# PCB.net
KiCad netlist of a schematic drawn in Altium Designer
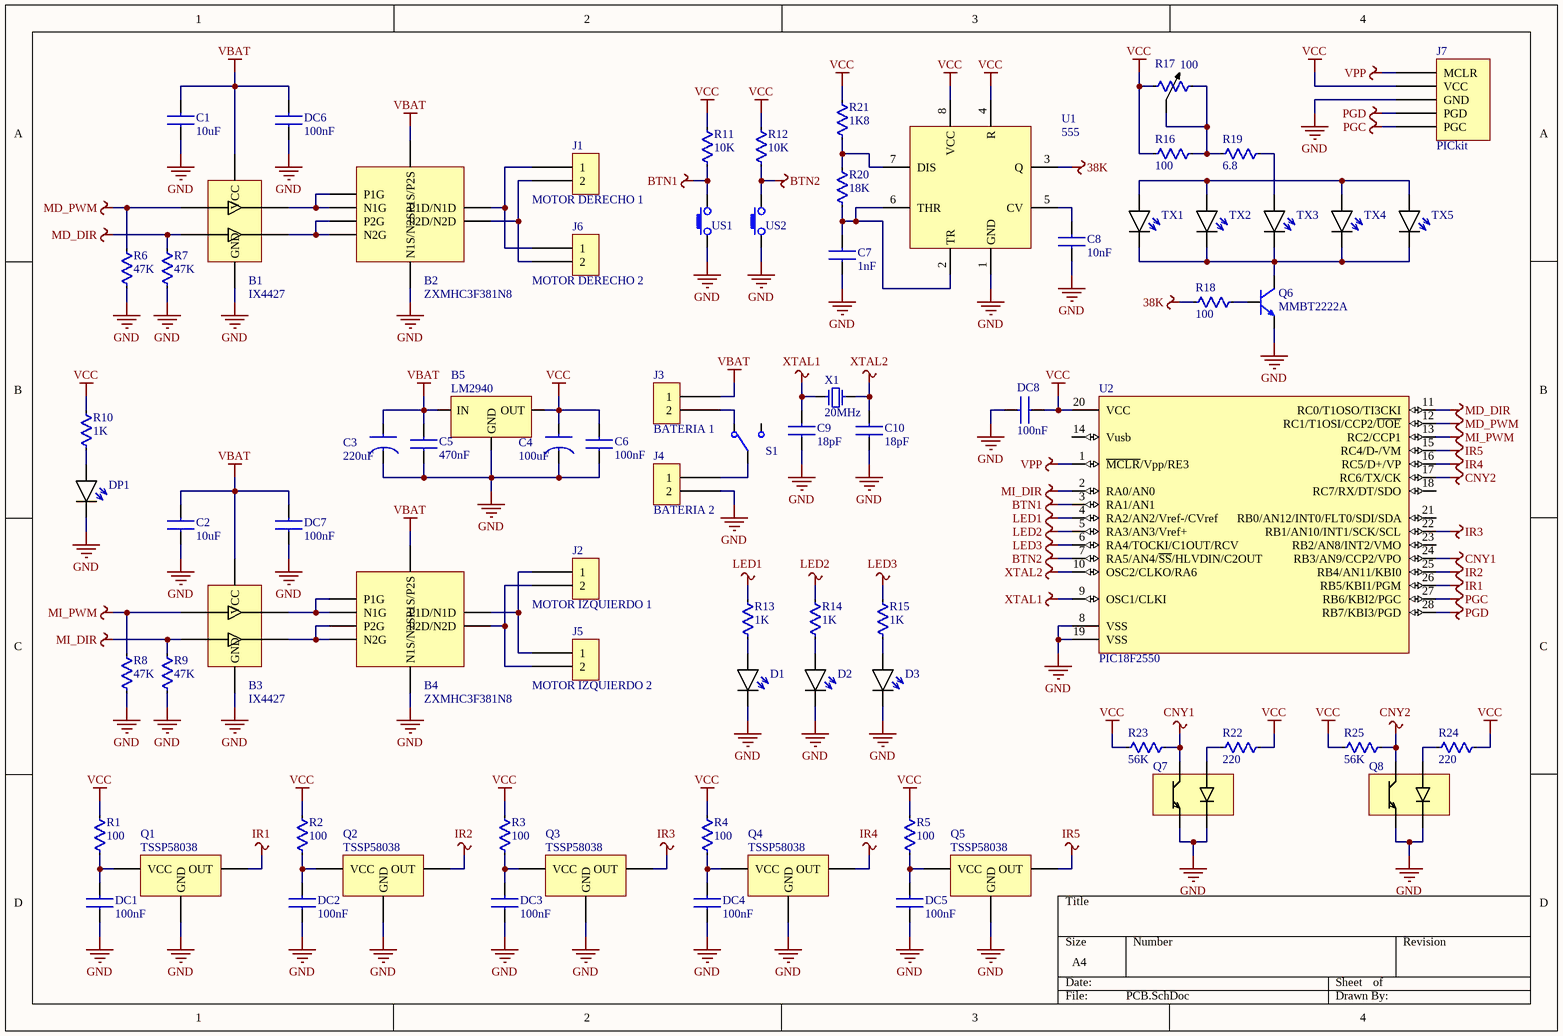
[diagram p0: PCB.SchDoc]

(export (version "E")
  (design (tool "Eeschema 10.0.6"))
  (components
    (comp (ref "B1") (value "IX4427") (footprint "SOIC-8") (libsource (lib "AltiumLibrary") (part "4427")))
    (comp (ref "B2")
      (value "ZXMHC3F381N8")
      (footprint "SOIC-8")
      (libsource (lib "AltiumLibrary") (part "ZXMHC3F381N8"))
    )
    (comp (ref "B3") (value "IX4427") (footprint "SOIC-8") (libsource (lib "AltiumLibrary") (part "4427")))
    (comp (ref "B4")
      (value "ZXMHC3F381N8")
      (footprint "SOIC-8")
      (libsource (lib "AltiumLibrary") (part "ZXMHC3F381N8"))
    )
    (comp (ref "B5") (value "LM2940") (footprint "TO-263") (libsource (lib "AltiumLibrary") (part "LM2940")))
    (comp (ref "C1")
      (value "10uF")
      (footprint "C1206")
      (fields (field (name "Comment") "CAP-CER"))
      (libsource (lib "AltiumLibrary") (part "CAP-CER"))
    )
    (comp (ref "C2")
      (value "10uF")
      (footprint "C1206")
      (fields (field (name "Comment") "CAP-CER"))
      (libsource (lib "AltiumLibrary") (part "CAP-CER"))
    )
    (comp (ref "C3")
      (value "220uF")
      (footprint "CAP-ELEC-5x11x2mm")
      (fields (field (name "Comment") "CAP-ELEC"))
      (libsource (lib "AltiumLibrary") (part "CAP-ELEC"))
    )
    (comp (ref "C4")
      (value "100uF")
      (footprint "CAP-ELEC-5x11x2mm")
      (fields (field (name "Comment") "CAP-ELEC"))
      (libsource (lib "AltiumLibrary") (part "CAP-ELEC"))
    )
    (comp (ref "C5")
      (value "470nF")
      (footprint "C1206")
      (fields (field (name "Comment") "CAP-CER"))
      (libsource (lib "AltiumLibrary") (part "CAP-CER"))
    )
    (comp (ref "C6")
      (value "100nF")
      (footprint "C1206")
      (fields (field (name "Comment") "CAP-CER"))
      (libsource (lib "AltiumLibrary") (part "CAP-CER"))
    )
    (comp (ref "C7")
      (value "1nF")
      (footprint "C1206")
      (fields (field (name "Comment") "CAP-CER"))
      (libsource (lib "AltiumLibrary") (part "CAP-CER"))
    )
    (comp (ref "C8")
      (value "10nF")
      (footprint "C1206")
      (fields (field (name "Comment") "CAP-CER"))
      (libsource (lib "AltiumLibrary") (part "CAP-CER"))
    )
    (comp (ref "C9")
      (value "18pF")
      (footprint "C1206")
      (fields (field (name "Comment") "CAP-CER"))
      (libsource (lib "AltiumLibrary") (part "CAP-CER"))
    )
    (comp (ref "C10")
      (value "18pF")
      (footprint "C1206")
      (fields (field (name "Comment") "CAP-CER"))
      (libsource (lib "AltiumLibrary") (part "CAP-CER"))
    )
    (comp (ref "D1") (value "LED") (footprint "LED-3MM-RED") (libsource (lib "AltiumLibrary") (part "LED")))
    (comp (ref "D2")
      (value "LED")
      (footprint "LED-3MM-YELLOW")
      (libsource (lib "AltiumLibrary") (part "LED"))
    )
    (comp (ref "D3") (value "LED") (footprint "LED-3MM-GREEN") (libsource (lib "AltiumLibrary") (part "LED")))
    (comp (ref "DC1")
      (value "100nF")
      (footprint "C1206")
      (fields (field (name "Comment") "CAP-CER"))
      (libsource (lib "AltiumLibrary") (part "CAP-CER"))
    )
    (comp (ref "DC2")
      (value "100nF")
      (footprint "C1206")
      (fields (field (name "Comment") "CAP-CER"))
      (libsource (lib "AltiumLibrary") (part "CAP-CER"))
    )
    (comp (ref "DC3")
      (value "100nF")
      (footprint "C1206")
      (fields (field (name "Comment") "CAP-CER"))
      (libsource (lib "AltiumLibrary") (part "CAP-CER"))
    )
    (comp (ref "DC4")
      (value "100nF")
      (footprint "C1206")
      (fields (field (name "Comment") "CAP-CER"))
      (libsource (lib "AltiumLibrary") (part "CAP-CER"))
    )
    (comp (ref "DC5")
      (value "100nF")
      (footprint "C1206")
      (fields (field (name "Comment") "CAP-CER"))
      (libsource (lib "AltiumLibrary") (part "CAP-CER"))
    )
    (comp (ref "DC6")
      (value "100nF")
      (footprint "C1206")
      (fields (field (name "Comment") "CAP-CER"))
      (libsource (lib "AltiumLibrary") (part "CAP-CER"))
    )
    (comp (ref "DC7")
      (value "100nF")
      (footprint "C1206")
      (fields (field (name "Comment") "CAP-CER"))
      (libsource (lib "AltiumLibrary") (part "CAP-CER"))
    )
    (comp (ref "DC8")
      (value "100nF")
      (footprint "C1206")
      (fields (field (name "Comment") "CAP-CER"))
      (libsource (lib "AltiumLibrary") (part "CAP-CER"))
    )
    (comp (ref "DP1") (value "LED") (footprint "LED-3MM-RED") (libsource (lib "AltiumLibrary") (part "LED")))
    (comp (ref "J1")
      (value "MOTOR DERECHO 1")
      (footprint "HEADER 1x2")
      (libsource (lib "") (part "Header 1x2_1"))
    )
    (comp (ref "J2")
      (value "MOTOR IZQUIERDO 1")
      (footprint "HEADER 1x2")
      (libsource (lib "") (part "Header 1x2_1"))
    )
    (comp (ref "J3")
      (value "BATERIA 1")
      (footprint "HEADER 1x2")
      (libsource (lib "AltiumLibrary") (part "Header 1x2"))
    )
    (comp (ref "J4")
      (value "BATERIA 2")
      (footprint "HEADER 1x2")
      (libsource (lib "AltiumLibrary") (part "Header 1x2"))
    )
    (comp (ref "J5")
      (value "MOTOR IZQUIERDO 2")
      (footprint "HEADER 1x2")
      (libsource (lib "") (part "Header 1x2_1"))
    )
    (comp (ref "J6")
      (value "MOTOR DERECHO 2")
      (footprint "HEADER 1x2")
      (libsource (lib "") (part "Header 1x2_1"))
    )
    (comp (ref "J7")
      (value "PICkit")
      (footprint "Header 1x5")
      (libsource (lib "AltiumLibrary") (part "PICkit"))
    )
    (comp (ref "Q1")
      (value "TSSP58038")
      (footprint "TSSP58038")
      (libsource (lib "AltiumLibrary") (part "TSSP58038"))
    )
    (comp (ref "Q2")
      (value "TSSP58038")
      (footprint "TSSP58038")
      (libsource (lib "AltiumLibrary") (part "TSSP58038"))
    )
    (comp (ref "Q3")
      (value "TSSP58038")
      (footprint "TSSP58038")
      (libsource (lib "AltiumLibrary") (part "TSSP58038"))
    )
    (comp (ref "Q4")
      (value "TSSP58038")
      (footprint "TSSP58038")
      (libsource (lib "AltiumLibrary") (part "TSSP58038"))
    )
    (comp (ref "Q5")
      (value "TSSP58038")
      (footprint "TSSP58038")
      (libsource (lib "AltiumLibrary") (part "TSSP58038"))
    )
    (comp (ref "Q6") (value "MMBT2222A") (footprint "SOT-23") (libsource (lib "AltiumLibrary") (part "NPN")))
    (comp (ref "Q7")
      (value "QRE1113GR")
      (footprint "QRE1113GR")
      (fields (field (name "MF") "ON Semiconductor"))
      (libsource (lib "AltiumLibrary") (part "QRE1113GR"))
    )
    (comp (ref "Q8")
      (value "QRE1113GR")
      (footprint "QRE1113GR")
      (fields (field (name "MF") "ON Semiconductor"))
      (libsource (lib "AltiumLibrary") (part "QRE1113GR"))
    )
    (comp (ref "R1")
      (value "100")
      (footprint "R1206")
      (fields (field (name "Comment") "RES"))
      (libsource (lib "AltiumLibrary") (part "RES"))
    )
    (comp (ref "R2")
      (value "100")
      (footprint "R1206")
      (fields (field (name "Comment") "RES"))
      (libsource (lib "AltiumLibrary") (part "RES"))
    )
    (comp (ref "R3")
      (value "100")
      (footprint "R1206")
      (fields (field (name "Comment") "RES"))
      (libsource (lib "AltiumLibrary") (part "RES"))
    )
    (comp (ref "R4")
      (value "100")
      (footprint "R1206")
      (fields (field (name "Comment") "RES"))
      (libsource (lib "AltiumLibrary") (part "RES"))
    )
    (comp (ref "R5")
      (value "100")
      (footprint "R1206")
      (fields (field (name "Comment") "RES"))
      (libsource (lib "AltiumLibrary") (part "RES"))
    )
    (comp (ref "R6")
      (value "47K")
      (footprint "R1206")
      (fields (field (name "Comment") "RES"))
      (libsource (lib "AltiumLibrary") (part "RES"))
    )
    (comp (ref "R7")
      (value "47K")
      (footprint "R1206")
      (fields (field (name "Comment") "RES"))
      (libsource (lib "AltiumLibrary") (part "RES"))
    )
    (comp (ref "R8")
      (value "47K")
      (footprint "R1206")
      (fields (field (name "Comment") "RES"))
      (libsource (lib "AltiumLibrary") (part "RES"))
    )
    (comp (ref "R9")
      (value "47K")
      (footprint "R1206")
      (fields (field (name "Comment") "RES"))
      (libsource (lib "AltiumLibrary") (part "RES"))
    )
    (comp (ref "R10")
      (value "1K")
      (footprint "R1206")
      (fields (field (name "Comment") "RES"))
      (libsource (lib "AltiumLibrary") (part "RES"))
    )
    (comp (ref "R11")
      (value "10K")
      (footprint "R1206")
      (fields (field (name "Comment") "RES"))
      (libsource (lib "AltiumLibrary") (part "RES"))
    )
    (comp (ref "R12")
      (value "10K")
      (footprint "R1206")
      (fields (field (name "Comment") "RES"))
      (libsource (lib "AltiumLibrary") (part "RES"))
    )
    (comp (ref "R13")
      (value "1K")
      (footprint "R1206")
      (fields (field (name "Comment") "RES"))
      (libsource (lib "AltiumLibrary") (part "RES"))
    )
    (comp (ref "R14")
      (value "1K")
      (footprint "R1206")
      (fields (field (name "Comment") "RES"))
      (libsource (lib "AltiumLibrary") (part "RES"))
    )
    (comp (ref "R15")
      (value "1K")
      (footprint "R1206")
      (fields (field (name "Comment") "RES"))
      (libsource (lib "AltiumLibrary") (part "RES"))
    )
    (comp (ref "R16")
      (value "100")
      (footprint "R1206")
      (fields (field (name "Comment") "RES"))
      (libsource (lib "") (part "RES_1"))
    )
    (comp (ref "R17")
      (value "100")
      (footprint "TRIMPOT")
      (fields (field (name "Comment") "POT"))
      (libsource (lib "AltiumLibrary") (part "POT"))
    )
    (comp (ref "R18")
      (value "100")
      (footprint "R1206")
      (fields (field (name "Comment") "RES"))
      (libsource (lib "") (part "RES_2"))
    )
    (comp (ref "R19")
      (value "6.8")
      (footprint "R1206")
      (fields (field (name "Comment") "RES"))
      (libsource (lib "") (part "RES_1"))
    )
    (comp (ref "R20")
      (value "18K")
      (footprint "R1206")
      (fields (field (name "Comment") "RES"))
      (libsource (lib "AltiumLibrary") (part "RES"))
    )
    (comp (ref "R21")
      (value "1K8")
      (footprint "R1206")
      (fields (field (name "Comment") "RES"))
      (libsource (lib "AltiumLibrary") (part "RES"))
    )
    (comp (ref "R22")
      (value "220")
      (footprint "R1206")
      (fields (field (name "Comment") "RES"))
      (libsource (lib "") (part "RES_1"))
    )
    (comp (ref "R23")
      (value "56K")
      (footprint "R1206")
      (fields (field (name "Comment") "RES"))
      (libsource (lib "") (part "RES_1"))
    )
    (comp (ref "R24")
      (value "220")
      (footprint "R1206")
      (fields (field (name "Comment") "RES"))
      (libsource (lib "") (part "RES_1"))
    )
    (comp (ref "R25")
      (value "56K")
      (footprint "R1206")
      (fields (field (name "Comment") "RES"))
      (libsource (lib "") (part "RES_1"))
    )
    (comp (ref "S1")
      (value "SLIDE-SWITCH")
      (footprint "SWITCH")
      (libsource (lib "AltiumLibrary") (part "SLIDE-SWITCH"))
    )
    (comp (ref "TX1")
      (value "LED")
      (footprint "LED-5MM-CLEAR")
      (libsource (lib "AltiumLibrary") (part "LED"))
    )
    (comp (ref "TX2")
      (value "LED")
      (footprint "LED-5MM-CLEAR")
      (libsource (lib "AltiumLibrary") (part "LED"))
    )
    (comp (ref "TX3")
      (value "LED")
      (footprint "LED-5MM-CLEAR")
      (libsource (lib "AltiumLibrary") (part "LED"))
    )
    (comp (ref "TX4")
      (value "LED")
      (footprint "LED-5MM-CLEAR")
      (libsource (lib "AltiumLibrary") (part "LED"))
    )
    (comp (ref "TX5")
      (value "LED")
      (footprint "LED-5MM-CLEAR")
      (libsource (lib "AltiumLibrary") (part "LED"))
    )
    (comp (ref "U1") (value "555") (footprint "SOIC-8") (libsource (lib "AltiumLibrary") (part "555")))
    (comp (ref "U2")
      (value "PIC18F2550")
      (footprint "SOIC-SO28_N")
      (libsource (lib "AltiumLibrary") (part "PIC18F2550"))
    )
    (comp (ref "US1")
      (value "BUTTON")
      (footprint "TACT_SWITCH-SMALL-4PIN")
      (libsource (lib "AltiumLibrary") (part "BUTTON"))
    )
    (comp (ref "US2")
      (value "BUTTON")
      (footprint "TACT_SWITCH-SMALL-4PIN")
      (libsource (lib "AltiumLibrary") (part "BUTTON"))
    )
    (comp (ref "X1")
      (value "XTAL")
      (footprint "HC-49/S")
      (fields (field (name "FREQUENCY") "20MHz"))
      (libsource (lib "AltiumLibrary") (part "XTAL"))
    )
  )
  (nets
    (net (code "1") (name "38K") (class "Default")
      (node (ref "R18") (pin "1") (pintype "passive"))
      (node (ref "U1") (pin "3") (pinfunction "Q_3") (pintype "passive"))
    )
    (net (code "2") (name "BTN1") (class "Default")
      (node (ref "R11") (pin "1") (pintype "passive"))
      (node (ref "U2") (pin "3") (pinfunction "RA1/AN1_3") (pintype "bidirectional"))
      (node (ref "US1") (pin "2") (pintype "passive"))
    )
    (net (code "3") (name "BTN2") (class "Default")
      (node (ref "R12") (pin "1") (pintype "passive"))
      (node (ref "U2") (pin "7") (pinfunction "RA5/AN4/~{SS}/HLVDIN/C2OUT_7") (pintype "bidirectional"))
      (node (ref "US2") (pin "2") (pintype "passive"))
    )
    (net (code "4") (name "CNY1") (class "Default")
      (node (ref "Q7") (pin "C") (pinfunction "C_C") (pintype "passive"))
      (node (ref "R23") (pin "1") (pintype "passive"))
      (node (ref "U2") (pin "24") (pinfunction "RB3/AN9/CCP2/VPO_24") (pintype "bidirectional"))
    )
    (net (code "5") (name "CNY2") (class "Default")
      (node (ref "Q8") (pin "C") (pinfunction "C_C") (pintype "passive"))
      (node (ref "R25") (pin "1") (pintype "passive"))
      (node (ref "U2") (pin "17") (pinfunction "RC6/TX/CK_17") (pintype "bidirectional"))
    )
    (net (code "6") (name "GND") (class "Default")
      (node (ref "B1") (pin "3") (pinfunction "GND_3") (pintype "passive"))
      (node (ref "B2") (pin "3") (pinfunction "N1S/N2S_3") (pintype "passive"))
      (node (ref "B3") (pin "3") (pinfunction "GND_3") (pintype "passive"))
      (node (ref "B4") (pin "3") (pinfunction "N1S/N2S_3") (pintype "passive"))
      (node (ref "B5") (pin "2") (pinfunction "GND_2") (pintype "power_in"))
      (node (ref "C1") (pin "2") (pintype "passive"))
      (node (ref "C10") (pin "1") (pintype "passive"))
      (node (ref "C2") (pin "2") (pintype "passive"))
      (node (ref "C3") (pin "2") (pintype "passive"))
      (node (ref "C4") (pin "2") (pintype "passive"))
      (node (ref "C5") (pin "1") (pintype "passive"))
      (node (ref "C6") (pin "1") (pintype "passive"))
      (node (ref "C7") (pin "1") (pintype "passive"))
      (node (ref "C8") (pin "1") (pintype "passive"))
      (node (ref "C9") (pin "1") (pintype "passive"))
      (node (ref "D1") (pin "K") (pintype "passive"))
      (node (ref "D2") (pin "K") (pintype "passive"))
      (node (ref "D3") (pin "K") (pintype "passive"))
      (node (ref "DC1") (pin "2") (pintype "passive"))
      (node (ref "DC2") (pin "2") (pintype "passive"))
      (node (ref "DC3") (pin "2") (pintype "passive"))
      (node (ref "DC4") (pin "2") (pintype "passive"))
      (node (ref "DC5") (pin "2") (pintype "passive"))
      (node (ref "DC6") (pin "2") (pintype "passive"))
      (node (ref "DC7") (pin "2") (pintype "passive"))
      (node (ref "DC8") (pin "1") (pintype "passive"))
      (node (ref "DP1") (pin "K") (pintype "passive"))
      (node (ref "J4") (pin "2") (pinfunction "2_2") (pintype "passive"))
      (node (ref "J7") (pin "3") (pinfunction "GND_3") (pintype "power_in"))
      (node (ref "Q1") (pin "2") (pinfunction "GND_2") (pintype "passive"))
      (node (ref "Q2") (pin "2") (pinfunction "GND_2") (pintype "passive"))
      (node (ref "Q3") (pin "2") (pinfunction "GND_2") (pintype "passive"))
      (node (ref "Q4") (pin "2") (pinfunction "GND_2") (pintype "passive"))
      (node (ref "Q5") (pin "2") (pinfunction "GND_2") (pintype "passive"))
      (node (ref "Q6") (pin "E") (pinfunction "E_E") (pintype "passive"))
      (node (ref "Q7") (pin "E") (pinfunction "E_E") (pintype "passive"))
      (node (ref "Q7") (pin "K") (pinfunction "K_K") (pintype "passive"))
      (node (ref "Q8") (pin "E") (pinfunction "E_E") (pintype "passive"))
      (node (ref "Q8") (pin "K") (pinfunction "K_K") (pintype "passive"))
      (node (ref "R6") (pin "1") (pintype "passive"))
      (node (ref "R7") (pin "1") (pintype "passive"))
      (node (ref "R8") (pin "1") (pintype "passive"))
      (node (ref "R9") (pin "1") (pintype "passive"))
      (node (ref "U1") (pin "1") (pinfunction "GND_1") (pintype "passive"))
      (node (ref "U2") (pin "19") (pinfunction "VSS_19") (pintype "power_in"))
      (node (ref "U2") (pin "8") (pinfunction "VSS_8") (pintype "power_in"))
      (node (ref "US1") (pin "1") (pintype "passive"))
      (node (ref "US2") (pin "1") (pintype "passive"))
    )
    (net (code "7") (name "IR1") (class "Default")
      (node (ref "Q1") (pin "1") (pinfunction "OUT_1") (pintype "passive"))
      (node (ref "U2") (pin "26") (pinfunction "RB5/KBI1/PGM_26") (pintype "bidirectional"))
    )
    (net (code "8") (name "IR2") (class "Default")
      (node (ref "Q2") (pin "1") (pinfunction "OUT_1") (pintype "passive"))
      (node (ref "U2") (pin "25") (pinfunction "RB4/AN11/KBI0_25") (pintype "bidirectional"))
    )
    (net (code "9") (name "IR3") (class "Default")
      (node (ref "Q3") (pin "1") (pinfunction "OUT_1") (pintype "passive"))
      (node (ref "U2") (pin "22") (pinfunction "RB1/AN10/INT1/SCK/SCL_22") (pintype "bidirectional"))
    )
    (net (code "10") (name "IR4") (class "Default")
      (node (ref "Q4") (pin "1") (pinfunction "OUT_1") (pintype "passive"))
      (node (ref "U2") (pin "16") (pinfunction "RC5/D+/VP_16") (pintype "bidirectional"))
    )
    (net (code "11") (name "IR5") (class "Default")
      (node (ref "Q5") (pin "1") (pinfunction "OUT_1") (pintype "passive"))
      (node (ref "U2") (pin "15") (pinfunction "RC4/D-/VM_15") (pintype "bidirectional"))
    )
    (net (code "12") (name "LED1") (class "Default")
      (node (ref "R13") (pin "2") (pintype "passive"))
      (node (ref "U2") (pin "4") (pinfunction "RA2/AN2/Vref-/CVref_4") (pintype "bidirectional"))
    )
    (net (code "13") (name "LED2") (class "Default")
      (node (ref "R14") (pin "2") (pintype "passive"))
      (node (ref "U2") (pin "5") (pinfunction "RA3/AN3/Vref+_5") (pintype "bidirectional"))
    )
    (net (code "14") (name "LED3") (class "Default")
      (node (ref "R15") (pin "2") (pintype "passive"))
      (node (ref "U2") (pin "6") (pinfunction "RA4/TOCKI/C1OUT/RCV_6") (pintype "bidirectional"))
    )
    (net (code "15") (name "MD_DIR") (class "Default")
      (node (ref "B1") (pin "4") (pinfunction "INB_4") (pintype "passive"))
      (node (ref "R7") (pin "2") (pintype "passive"))
      (node (ref "U2") (pin "11") (pinfunction "RC0/T1OSO/TI3CKI_11") (pintype "bidirectional"))
    )
    (net (code "16") (name "MD_PWM") (class "Default")
      (node (ref "B1") (pin "2") (pinfunction "INA_2") (pintype "passive"))
      (node (ref "R6") (pin "2") (pintype "passive"))
      (node (ref "U2") (pin "12") (pinfunction "RC1/T1OSI/CCP2/~{UOE}_12") (pintype "bidirectional"))
    )
    (net (code "17") (name "MI_DIR") (class "Default")
      (node (ref "B3") (pin "4") (pinfunction "INB_4") (pintype "passive"))
      (node (ref "R9") (pin "2") (pintype "passive"))
      (node (ref "U2") (pin "2") (pinfunction "RA0/AN0_2") (pintype "bidirectional"))
    )
    (net (code "18") (name "MI_PWM") (class "Default")
      (node (ref "B3") (pin "2") (pinfunction "INA_2") (pintype "passive"))
      (node (ref "R8") (pin "2") (pintype "passive"))
      (node (ref "U2") (pin "13") (pinfunction "RC2/CCP1_13") (pintype "bidirectional"))
    )
    (net (code "19") (name "Net-(B1-OUTA)") (class "Default")
      (node (ref "B1") (pin "7") (pinfunction "OUTA_7") (pintype "passive"))
      (node (ref "B2") (pin "1") (pinfunction "N1G_1") (pintype "passive"))
      (node (ref "B2") (pin "8") (pinfunction "P1G_8") (pintype "passive"))
    )
    (net (code "20") (name "Net-(B1-OUTB)") (class "Default")
      (node (ref "B1") (pin "5") (pinfunction "OUTB_5") (pintype "passive"))
      (node (ref "B2") (pin "4") (pinfunction "N2G_4") (pintype "passive"))
      (node (ref "B2") (pin "5") (pinfunction "P2G_5") (pintype "passive"))
    )
    (net (code "21") (name "Net-(B2-P1D{slash}N1D)") (class "Default")
      (node (ref "B2") (pin "2") (pinfunction "P1D/N1D_2") (pintype "passive"))
      (node (ref "J1") (pin "1") (pinfunction "1_1") (pintype "passive"))
      (node (ref "J6") (pin "1") (pinfunction "1_1") (pintype "passive"))
    )
    (net (code "22") (name "Net-(B2-P2D{slash}N2D)") (class "Default")
      (node (ref "B2") (pin "6") (pinfunction "P2D/N2D_6") (pintype "passive"))
      (node (ref "J1") (pin "2") (pinfunction "2_2") (pintype "passive"))
      (node (ref "J6") (pin "2") (pinfunction "2_2") (pintype "passive"))
    )
    (net (code "23") (name "Net-(B3-OUTA)") (class "Default")
      (node (ref "B3") (pin "7") (pinfunction "OUTA_7") (pintype "passive"))
      (node (ref "B4") (pin "1") (pinfunction "N1G_1") (pintype "passive"))
      (node (ref "B4") (pin "8") (pinfunction "P1G_8") (pintype "passive"))
    )
    (net (code "24") (name "Net-(B3-OUTB)") (class "Default")
      (node (ref "B3") (pin "5") (pinfunction "OUTB_5") (pintype "passive"))
      (node (ref "B4") (pin "4") (pinfunction "N2G_4") (pintype "passive"))
      (node (ref "B4") (pin "5") (pinfunction "P2G_5") (pintype "passive"))
    )
    (net (code "25") (name "Net-(B4-P1D{slash}N1D)") (class "Default")
      (node (ref "B4") (pin "2") (pinfunction "P1D/N1D_2") (pintype "passive"))
      (node (ref "J2") (pin "1") (pinfunction "1_1") (pintype "passive"))
      (node (ref "J5") (pin "1") (pinfunction "1_1") (pintype "passive"))
    )
    (net (code "26") (name "Net-(B4-P2D{slash}N2D)") (class "Default")
      (node (ref "B4") (pin "6") (pinfunction "P2D/N2D_6") (pintype "passive"))
      (node (ref "J2") (pin "2") (pinfunction "2_2") (pintype "passive"))
      (node (ref "J5") (pin "2") (pinfunction "2_2") (pintype "passive"))
    )
    (net (code "27") (name "Net-(D1-PadA)") (class "Default")
      (node (ref "D1") (pin "A") (pintype "passive"))
      (node (ref "R13") (pin "1") (pintype "passive"))
    )
    (net (code "28") (name "Net-(D2-PadA)") (class "Default")
      (node (ref "D2") (pin "A") (pintype "passive"))
      (node (ref "R14") (pin "1") (pintype "passive"))
    )
    (net (code "29") (name "Net-(D3-PadA)") (class "Default")
      (node (ref "D3") (pin "A") (pintype "passive"))
      (node (ref "R15") (pin "1") (pintype "passive"))
    )
    (net (code "30") (name "Net-(DP1-PadA)") (class "Default")
      (node (ref "DP1") (pin "A") (pintype "passive"))
      (node (ref "R10") (pin "1") (pintype "passive"))
    )
    (net (code "31") (name "Net-(J3-Pad2)") (class "Default")
      (node (ref "J3") (pin "2") (pinfunction "2_2") (pintype "passive"))
      (node (ref "S1") (pin "1") (pintype "power_in"))
    )
    (net (code "32") (name "Net-(J4-Pad1)") (class "Default")
      (node (ref "J4") (pin "1") (pinfunction "1_1") (pintype "passive"))
      (node (ref "S1") (pin "2") (pintype "power_in"))
    )
    (net (code "33") (name "Net-(Q1-VCC)") (class "Default")
      (node (ref "DC1") (pin "1") (pintype "passive"))
      (node (ref "Q1") (pin "3") (pinfunction "VCC_3") (pintype "passive"))
      (node (ref "R1") (pin "1") (pintype "passive"))
    )
    (net (code "34") (name "Net-(Q2-VCC)") (class "Default")
      (node (ref "DC2") (pin "1") (pintype "passive"))
      (node (ref "Q2") (pin "3") (pinfunction "VCC_3") (pintype "passive"))
      (node (ref "R2") (pin "1") (pintype "passive"))
    )
    (net (code "35") (name "Net-(Q3-VCC)") (class "Default")
      (node (ref "DC3") (pin "1") (pintype "passive"))
      (node (ref "Q3") (pin "3") (pinfunction "VCC_3") (pintype "passive"))
      (node (ref "R3") (pin "1") (pintype "passive"))
    )
    (net (code "36") (name "Net-(Q4-VCC)") (class "Default")
      (node (ref "DC4") (pin "1") (pintype "passive"))
      (node (ref "Q4") (pin "3") (pinfunction "VCC_3") (pintype "passive"))
      (node (ref "R4") (pin "1") (pintype "passive"))
    )
    (net (code "37") (name "Net-(Q5-VCC)") (class "Default")
      (node (ref "DC5") (pin "1") (pintype "passive"))
      (node (ref "Q5") (pin "3") (pinfunction "VCC_3") (pintype "passive"))
      (node (ref "R5") (pin "1") (pintype "passive"))
    )
    (net (code "38") (name "Net-(Q6-PadB)") (class "Default")
      (node (ref "Q6") (pin "B") (pinfunction "B_B") (pintype "passive"))
      (node (ref "R18") (pin "2") (pintype "passive"))
    )
    (net (code "39") (name "Net-(Q6-PadC)") (class "Default")
      (node (ref "Q6") (pin "C") (pinfunction "C_C") (pintype "passive"))
      (node (ref "TX1") (pin "K") (pintype "passive"))
      (node (ref "TX2") (pin "K") (pintype "passive"))
      (node (ref "TX3") (pin "K") (pintype "passive"))
      (node (ref "TX4") (pin "K") (pintype "passive"))
      (node (ref "TX5") (pin "K") (pintype "passive"))
    )
    (net (code "40") (name "Net-(Q7-PadA)") (class "Default")
      (node (ref "Q7") (pin "A") (pinfunction "A_A") (pintype "passive"))
      (node (ref "R22") (pin "2") (pintype "passive"))
    )
    (net (code "41") (name "Net-(Q8-PadA)") (class "Default")
      (node (ref "Q8") (pin "A") (pinfunction "A_A") (pintype "passive"))
      (node (ref "R24") (pin "2") (pintype "passive"))
    )
    (net (code "42") (name "Net-(R16-Pad1)") (class "Default")
      (node (ref "R16") (pin "1") (pintype "passive"))
      (node (ref "R17") (pin "1") (pintype "passive"))
      (node (ref "R17") (pin "2") (pintype "passive"))
      (node (ref "R19") (pin "2") (pintype "passive"))
    )
    (net (code "43") (name "Net-(R19-Pad1)") (class "Default")
      (node (ref "R19") (pin "1") (pintype "passive"))
      (node (ref "TX3") (pin "A") (pintype "passive"))
    )
    (net (code "44") (name "Net-(TX1-PadA)") (class "Default")
      (node (ref "TX1") (pin "A") (pintype "passive"))
      (node (ref "TX2") (pin "A") (pintype "passive"))
      (node (ref "TX4") (pin "A") (pintype "passive"))
      (node (ref "TX5") (pin "A") (pintype "passive"))
    )
    (net (code "45") (name "Net-(U1-CV)") (class "Default")
      (node (ref "C8") (pin "2") (pintype "passive"))
      (node (ref "U1") (pin "5") (pinfunction "CV_5") (pintype "passive"))
    )
    (net (code "46") (name "Net-(U1-DIS)") (class "Default")
      (node (ref "R20") (pin "2") (pintype "passive"))
      (node (ref "R21") (pin "1") (pintype "passive"))
      (node (ref "U1") (pin "7") (pinfunction "DIS_7") (pintype "passive"))
    )
    (net (code "47") (name "Net-(U1-THR)") (class "Default")
      (node (ref "C7") (pin "2") (pintype "passive"))
      (node (ref "R20") (pin "1") (pintype "passive"))
      (node (ref "U1") (pin "2") (pinfunction "TR_2") (pintype "passive"))
      (node (ref "U1") (pin "6") (pinfunction "THR_6") (pintype "passive"))
    )
    (net (code "48") (name "PGC") (class "Default")
      (node (ref "J7") (pin "5") (pinfunction "PGC_5") (pintype "passive"))
      (node (ref "U2") (pin "27") (pinfunction "RB6/KBI2/PGC_27") (pintype "bidirectional"))
    )
    (net (code "49") (name "PGD") (class "Default")
      (node (ref "J7") (pin "4") (pinfunction "PGD_4") (pintype "passive"))
      (node (ref "U2") (pin "28") (pinfunction "RB7/KBI3/PGD_28") (pintype "bidirectional"))
    )
    (net (code "50") (name "VBAT") (class "Default")
      (node (ref "B1") (pin "6") (pinfunction "VCC_6") (pintype "passive"))
      (node (ref "B2") (pin "7") (pinfunction "P1S/P2S_7") (pintype "passive"))
      (node (ref "B3") (pin "6") (pinfunction "VCC_6") (pintype "passive"))
      (node (ref "B4") (pin "7") (pinfunction "P1S/P2S_7") (pintype "passive"))
      (node (ref "B5") (pin "1") (pinfunction "IN_1") (pintype "power_in"))
      (node (ref "C1") (pin "1") (pintype "passive"))
      (node (ref "C2") (pin "1") (pintype "passive"))
      (node (ref "C3") (pin "1") (pintype "passive"))
      (node (ref "C5") (pin "2") (pintype "passive"))
      (node (ref "DC6") (pin "1") (pintype "passive"))
      (node (ref "DC7") (pin "1") (pintype "passive"))
      (node (ref "J3") (pin "1") (pinfunction "1_1") (pintype "passive"))
    )
    (net (code "51") (name "VCC") (class "Default")
      (node (ref "B5") (pin "3") (pinfunction "OUT_3") (pintype "power_in"))
      (node (ref "C4") (pin "1") (pintype "passive"))
      (node (ref "C6") (pin "2") (pintype "passive"))
      (node (ref "DC8") (pin "2") (pintype "passive"))
      (node (ref "J7") (pin "2") (pinfunction "VCC_2") (pintype "power_in"))
      (node (ref "R1") (pin "2") (pintype "passive"))
      (node (ref "R10") (pin "2") (pintype "passive"))
      (node (ref "R11") (pin "2") (pintype "passive"))
      (node (ref "R12") (pin "2") (pintype "passive"))
      (node (ref "R16") (pin "2") (pintype "passive"))
      (node (ref "R17") (pin "3") (pintype "passive"))
      (node (ref "R2") (pin "2") (pintype "passive"))
      (node (ref "R21") (pin "2") (pintype "passive"))
      (node (ref "R22") (pin "1") (pintype "passive"))
      (node (ref "R23") (pin "2") (pintype "passive"))
      (node (ref "R24") (pin "1") (pintype "passive"))
      (node (ref "R25") (pin "2") (pintype "passive"))
      (node (ref "R3") (pin "2") (pintype "passive"))
      (node (ref "R4") (pin "2") (pintype "passive"))
      (node (ref "R5") (pin "2") (pintype "passive"))
      (node (ref "U1") (pin "4") (pinfunction "R_4") (pintype "passive"))
      (node (ref "U1") (pin "8") (pinfunction "VCC_8") (pintype "passive"))
      (node (ref "U2") (pin "20") (pinfunction "VCC_20") (pintype "power_in"))
    )
    (net (code "52") (name "VPP") (class "Default")
      (node (ref "J7") (pin "1") (pinfunction "MCLR_1") (pintype "passive"))
      (node (ref "U2") (pin "1") (pinfunction "~{MCLR}/Vpp/RE3_1") (pintype "bidirectional"))
    )
    (net (code "53") (name "XTAL1") (class "Default")
      (node (ref "C9") (pin "2") (pintype "passive"))
      (node (ref "U2") (pin "9") (pinfunction "OSC1/CLKI_9") (pintype "bidirectional"))
      (node (ref "X1") (pin "2") (pintype "passive"))
    )
    (net (code "54") (name "XTAL2") (class "Default")
      (node (ref "C10") (pin "2") (pintype "passive"))
      (node (ref "U2") (pin "10") (pinfunction "OSC2/CLKO/RA6_10") (pintype "bidirectional"))
      (node (ref "X1") (pin "1") (pintype "passive"))
    )
    (net (code "55") (name "unconnected-(S1-Pad3)") (class "Default")
      (node (ref "S1") (pin "3") (pintype "power_in"))
    )
    (net (code "56") (name "unconnected-(U2-RB0{slash}AN12{slash}INT0{slash}FLT0{slash}SDI{slash}SDA-Pad21)") (class "Default")
      (node (ref "U2") (pin "21") (pinfunction "RB0/AN12/INT0/FLT0/SDI/SDA_21") (pintype "bidirectional"))
    )
    (net (code "57") (name "unconnected-(U2-RB2{slash}AN8{slash}INT2{slash}VMO-Pad23)") (class "Default")
      (node (ref "U2") (pin "23") (pinfunction "RB2/AN8/INT2/VMO_23") (pintype "bidirectional"))
    )
    (net (code "58") (name "unconnected-(U2-RC7{slash}RX{slash}DT{slash}SDO-Pad18)") (class "Default")
      (node (ref "U2") (pin "18") (pinfunction "RC7/RX/DT/SDO_18") (pintype "bidirectional"))
    )
    (net (code "59") (name "unconnected-(U2-Vusb-Pad14)") (class "Default")
      (node (ref "U2") (pin "14") (pinfunction "Vusb_14") (pintype "bidirectional"))
    )
  )
)
